# PCM2704_Test_v1.net
KiCad netlist of a schematic drawn in EAGLE
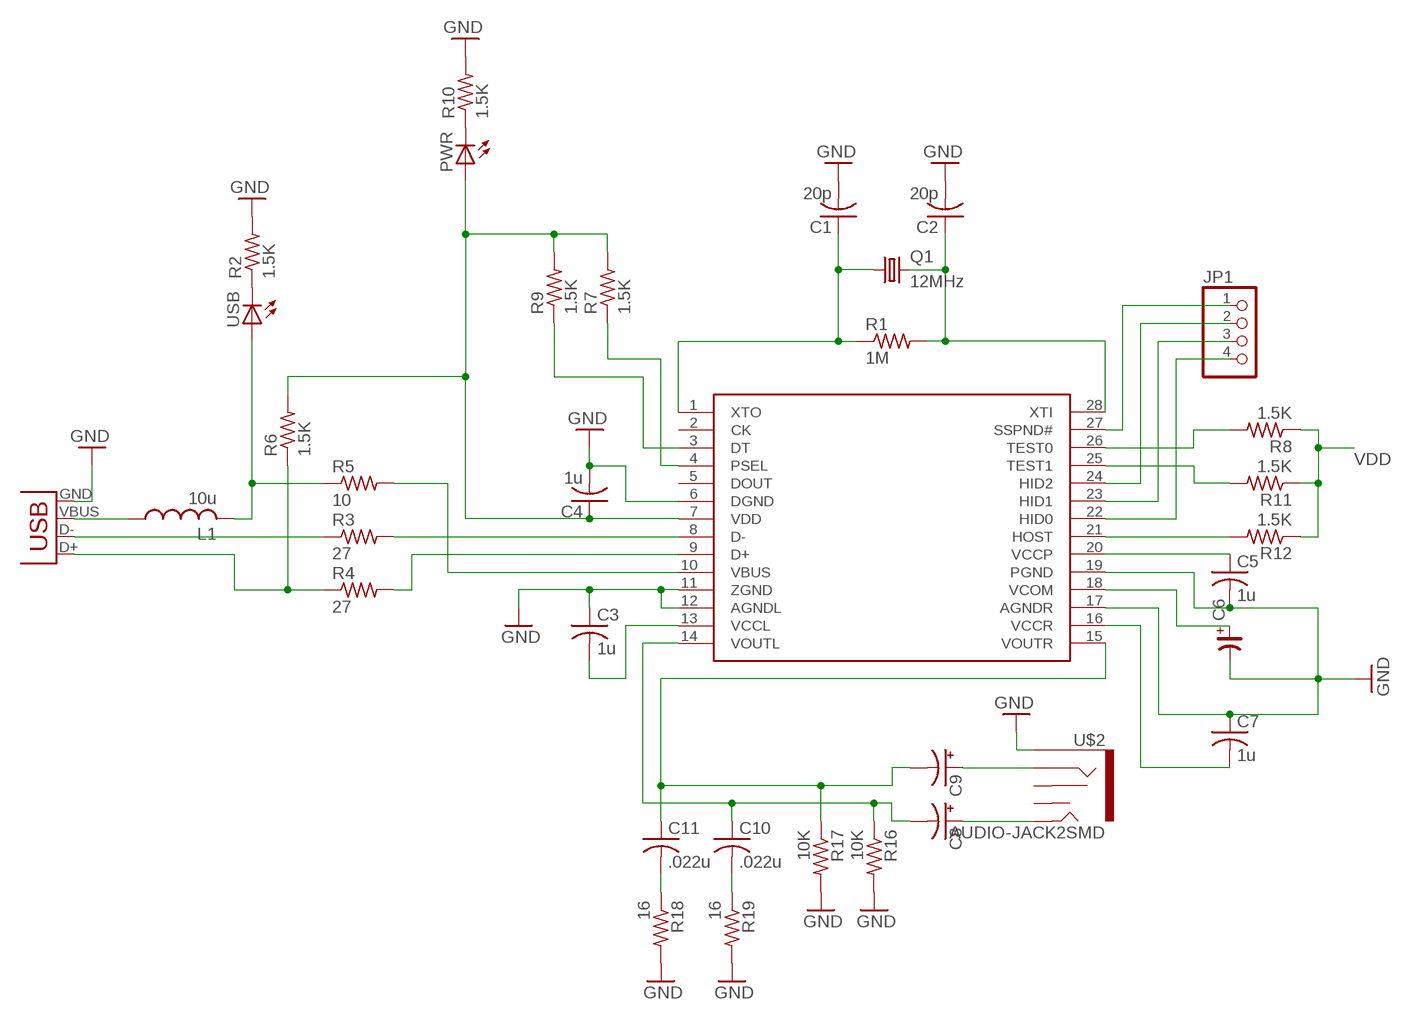
[diagram p0: schematic, sheet 1]

(export (version "E")
  (design (tool "Eeschema 10.0.6"))
  (components
    (comp (ref "C1")
      (value "20p")
      (footprint "eagle-import:C0603")
      (libsource (lib "eagle-import") (part "C-USC0603"))
    )
    (comp (ref "C2")
      (value "20p")
      (footprint "eagle-import:C0603")
      (libsource (lib "eagle-import") (part "C-USC0603"))
    )
    (comp (ref "C3")
      (value "1u")
      (footprint "eagle-import:C0603")
      (libsource (lib "eagle-import") (part "C-USC0603"))
    )
    (comp (ref "C4")
      (value "1u")
      (footprint "eagle-import:C0603")
      (libsource (lib "eagle-import") (part "C-USC0603"))
    )
    (comp (ref "C5")
      (value "1u")
      (footprint "eagle-import:C0603")
      (libsource (lib "eagle-import") (part "C-USC0603"))
    )
    (comp (ref "C6")
      (value "CP_E-010X030")
      (footprint "eagle-import:CE-010X030")
      (libsource (lib "eagle-import") (part "CP_E-010X030"))
    )
    (comp (ref "C7")
      (value "1u")
      (footprint "eagle-import:C0603")
      (libsource (lib "eagle-import") (part "C-USC0603"))
    )
    (comp (ref "C8")
      (value "CPOL-USE1.8-4")
      (footprint "eagle-import:E1,8-4")
      (libsource (lib "eagle-import") (part "CPOL-USE1.8-4"))
    )
    (comp (ref "C9")
      (value "CPOL-USE1.8-4")
      (footprint "eagle-import:E1,8-4")
      (libsource (lib "eagle-import") (part "CPOL-USE1.8-4"))
    )
    (comp (ref "C10")
      (value ".022u")
      (footprint "eagle-import:C0603")
      (libsource (lib "eagle-import") (part "C-USC0603"))
    )
    (comp (ref "C11")
      (value ".022u")
      (footprint "eagle-import:C0603")
      (libsource (lib "eagle-import") (part "C-USC0603"))
    )
    (comp (ref "JP1")
      (value "PINHD-1X4")
      (footprint "eagle-import:1X04")
      (libsource (lib "eagle-import") (part "PINHD-1X4"))
    )
    (comp (ref "L1")
      (value "10u")
      (footprint "eagle-import:L3225M")
      (libsource (lib "eagle-import") (part "L-USL3225M"))
    )
    (comp (ref "PWR")
      (value "LEDCHIP-LED0603")
      (footprint "eagle-import:CHIP-LED0603")
      (libsource (lib "eagle-import") (part "LEDCHIP-LED0603"))
    )
    (comp (ref "Q1")
      (value "12MHz")
      (footprint "eagle-import:HC49US")
      (libsource (lib "eagle-import") (part "CRYSTALHC49US"))
    )
    (comp (ref "R1")
      (value "1M")
      (footprint "eagle-import:R0603")
      (libsource (lib "eagle-import") (part "R-US_R0603"))
    )
    (comp (ref "R2")
      (value "1.5K")
      (footprint "eagle-import:R0603")
      (libsource (lib "eagle-import") (part "R-US_R0603"))
    )
    (comp (ref "R3")
      (value "27")
      (footprint "eagle-import:R0603")
      (libsource (lib "eagle-import") (part "R-US_R0603"))
    )
    (comp (ref "R4")
      (value "27")
      (footprint "eagle-import:R0603")
      (libsource (lib "eagle-import") (part "R-US_R0603"))
    )
    (comp (ref "R5")
      (value "10")
      (footprint "eagle-import:R0603")
      (libsource (lib "eagle-import") (part "R-US_R0603"))
    )
    (comp (ref "R6")
      (value "1.5K")
      (footprint "eagle-import:R0603")
      (libsource (lib "eagle-import") (part "R-US_R0603"))
    )
    (comp (ref "R7")
      (value "1.5K")
      (footprint "eagle-import:R0603")
      (libsource (lib "eagle-import") (part "R-US_R0603"))
    )
    (comp (ref "R8")
      (value "1.5K")
      (footprint "eagle-import:R0603")
      (libsource (lib "eagle-import") (part "R-US_R0603"))
    )
    (comp (ref "R9")
      (value "1.5K")
      (footprint "eagle-import:R0603")
      (libsource (lib "eagle-import") (part "R-US_R0603"))
    )
    (comp (ref "R10")
      (value "1.5K")
      (footprint "eagle-import:R0603")
      (libsource (lib "eagle-import") (part "R-US_R0603"))
    )
    (comp (ref "R11")
      (value "1.5K")
      (footprint "eagle-import:R0603")
      (libsource (lib "eagle-import") (part "R-US_R0603"))
    )
    (comp (ref "R12")
      (value "1.5K")
      (footprint "eagle-import:R0603")
      (libsource (lib "eagle-import") (part "R-US_R0603"))
    )
    (comp (ref "R16")
      (value "10K")
      (footprint "eagle-import:R0603")
      (libsource (lib "eagle-import") (part "R-US_R0603"))
    )
    (comp (ref "R17")
      (value "10K")
      (footprint "eagle-import:R0603")
      (libsource (lib "eagle-import") (part "R-US_R0603"))
    )
    (comp (ref "R18")
      (value "16")
      (footprint "eagle-import:R0603")
      (libsource (lib "eagle-import") (part "R-US_R0603"))
    )
    (comp (ref "R19")
      (value "16")
      (footprint "eagle-import:R0603")
      (libsource (lib "eagle-import") (part "R-US_R0603"))
    )
    (comp (ref "U$1")
      (value "PCM2704C")
      (footprint "eagle-import:PCM2704C")
      (libsource (lib "eagle-import") (part "PCM2704C"))
    )
    (comp (ref "U$2")
      (value "AUDIO-JACK2SMD")
      (footprint "eagle-import:AUDIO-JACK-3.5MM-SMD")
      (libsource (lib "eagle-import") (part "AUDIO-JACK2SMD"))
    )
    (comp (ref "USB")
      (value "LEDCHIP-LED0603")
      (footprint "eagle-import:CHIP-LED0603")
      (libsource (lib "eagle-import") (part "LEDCHIP-LED0603"))
    )
    (comp (ref "X1")
      (value "USB-MB-S")
      (footprint "eagle-import:USB-MB-S")
      (libsource (lib "eagle-import") (part "USB-MB-S"))
    )
  )
  (nets
    (net (code "1") (name "/VDD") (class "Default")
      (node (ref "C4") (pin "1") (pinfunction "1_1") (pintype "passive"))
      (node (ref "PWR") (pin "A") (pinfunction "A_A") (pintype "passive"))
      (node (ref "R11") (pin "1") (pinfunction "1_1") (pintype "passive"))
      (node (ref "R12") (pin "1") (pinfunction "1_1") (pintype "passive"))
      (node (ref "R6") (pin "2") (pinfunction "2_2") (pintype "passive"))
      (node (ref "R7") (pin "2") (pinfunction "2_2") (pintype "passive"))
      (node (ref "R8") (pin "1") (pinfunction "1_1") (pintype "passive"))
      (node (ref "R9") (pin "2") (pinfunction "2_2") (pintype "passive"))
      (node (ref "U$1") (pin "7") (pinfunction "VDD_7") (pintype "bidirectional"))
    )
    (net (code "2") (name "GND") (class "Default")
      (node (ref "C1") (pin "2") (pinfunction "2_2") (pintype "passive"))
      (node (ref "C2") (pin "2") (pinfunction "2_2") (pintype "passive"))
      (node (ref "C3") (pin "1") (pinfunction "1_1") (pintype "passive"))
      (node (ref "C4") (pin "2") (pinfunction "2_2") (pintype "passive"))
      (node (ref "C5") (pin "2") (pinfunction "2_2") (pintype "passive"))
      (node (ref "C6") (pin "-") (pinfunction "-_-") (pintype "passive"))
      (node (ref "C7") (pin "1") (pinfunction "1_1") (pintype "passive"))
      (node (ref "R10") (pin "2") (pinfunction "2_2") (pintype "passive"))
      (node (ref "R16") (pin "2") (pinfunction "2_2") (pintype "passive"))
      (node (ref "R17") (pin "2") (pinfunction "2_2") (pintype "passive"))
      (node (ref "R18") (pin "2") (pinfunction "2_2") (pintype "passive"))
      (node (ref "R19") (pin "2") (pinfunction "2_2") (pintype "passive"))
      (node (ref "R2") (pin "2") (pinfunction "2_2") (pintype "passive"))
      (node (ref "U$1") (pin "11") (pinfunction "ZGND_11") (pintype "bidirectional"))
      (node (ref "U$1") (pin "12") (pinfunction "AGNDL_12") (pintype "bidirectional"))
      (node (ref "U$1") (pin "17") (pinfunction "AGNDR_17") (pintype "bidirectional"))
      (node (ref "U$1") (pin "19") (pinfunction "PGND_19") (pintype "bidirectional"))
      (node (ref "U$1") (pin "6") (pinfunction "DGND_6") (pintype "bidirectional"))
      (node (ref "U$2") (pin "SLEEVE") (pinfunction "SLEEVE_SLEEVE") (pintype "bidirectional"))
      (node (ref "X1") (pin "GND") (pinfunction "GND_GND") (pintype "bidirectional"))
    )
    (net (code "3") (name "Net-(C8-Pad+)") (class "Default")
      (node (ref "C8") (pin "+") (pinfunction "+_+") (pintype "passive"))
      (node (ref "U$2") (pin "TIP") (pinfunction "TIP_TIP") (pintype "bidirectional"))
    )
    (net (code "4") (name "Net-(C9-Pad+)") (class "Default")
      (node (ref "C9") (pin "+") (pinfunction "+_+") (pintype "passive"))
      (node (ref "U$2") (pin "RING") (pinfunction "RING_RING") (pintype "bidirectional"))
    )
    (net (code "5") (name "Net-(C10-Pad2)") (class "Default")
      (node (ref "C10") (pin "2") (pinfunction "2_2") (pintype "passive"))
      (node (ref "R19") (pin "1") (pinfunction "1_1") (pintype "passive"))
    )
    (net (code "6") (name "Net-(C11-Pad2)") (class "Default")
      (node (ref "C11") (pin "2") (pinfunction "2_2") (pintype "passive"))
      (node (ref "R18") (pin "1") (pinfunction "1_1") (pintype "passive"))
    )
    (net (code "7") (name "Net-(L1-Pad1)") (class "Default")
      (node (ref "L1") (pin "1") (pinfunction "1_1") (pintype "passive"))
      (node (ref "X1") (pin "VBUS") (pinfunction "VBUS_VBUS") (pintype "bidirectional"))
    )
    (net (code "8") (name "Net-(L1-Pad2)") (class "Default")
      (node (ref "L1") (pin "2") (pinfunction "2_2") (pintype "passive"))
      (node (ref "R5") (pin "1") (pinfunction "1_1") (pintype "passive"))
      (node (ref "USB") (pin "A") (pinfunction "A_A") (pintype "passive"))
    )
    (net (code "9") (name "Net-(PWR-PadC)") (class "Default")
      (node (ref "PWR") (pin "C") (pinfunction "C_C") (pintype "passive"))
      (node (ref "R10") (pin "1") (pinfunction "1_1") (pintype "passive"))
    )
    (net (code "10") (name "Net-(R2-Pad1)") (class "Default")
      (node (ref "R2") (pin "1") (pinfunction "1_1") (pintype "passive"))
      (node (ref "USB") (pin "C") (pinfunction "C_C") (pintype "passive"))
    )
    (net (code "11") (name "Net-(R3-Pad1)") (class "Default")
      (node (ref "R3") (pin "1") (pinfunction "1_1") (pintype "passive"))
      (node (ref "X1") (pin "D-") (pinfunction "D-_D-") (pintype "bidirectional"))
    )
    (net (code "12") (name "Net-(R4-Pad1)") (class "Default")
      (node (ref "R4") (pin "1") (pinfunction "1_1") (pintype "passive"))
      (node (ref "R6") (pin "1") (pinfunction "1_1") (pintype "passive"))
      (node (ref "X1") (pin "D+") (pinfunction "D+_D+") (pintype "bidirectional"))
    )
    (net (code "13") (name "Net-(U$1-D+)") (class "Default")
      (node (ref "R4") (pin "2") (pinfunction "2_2") (pintype "passive"))
      (node (ref "U$1") (pin "9") (pinfunction "D+_9") (pintype "bidirectional"))
    )
    (net (code "14") (name "Net-(U$1-D-)") (class "Default")
      (node (ref "R3") (pin "2") (pinfunction "2_2") (pintype "passive"))
      (node (ref "U$1") (pin "8") (pinfunction "D-_8") (pintype "bidirectional"))
    )
    (net (code "15") (name "Net-(U$1-DT)") (class "Default")
      (node (ref "R9") (pin "1") (pinfunction "1_1") (pintype "passive"))
      (node (ref "U$1") (pin "3") (pinfunction "DT_3") (pintype "bidirectional"))
    )
    (net (code "16") (name "Net-(U$1-HID0)") (class "Default")
      (node (ref "JP1") (pin "4") (pinfunction "4_4") (pintype "passive"))
      (node (ref "U$1") (pin "22") (pinfunction "HID0_22") (pintype "bidirectional"))
    )
    (net (code "17") (name "Net-(U$1-HID1)") (class "Default")
      (node (ref "JP1") (pin "3") (pinfunction "3_3") (pintype "passive"))
      (node (ref "U$1") (pin "23") (pinfunction "HID1_23") (pintype "bidirectional"))
    )
    (net (code "18") (name "Net-(U$1-HID2)") (class "Default")
      (node (ref "JP1") (pin "2") (pinfunction "2_2") (pintype "passive"))
      (node (ref "U$1") (pin "24") (pinfunction "HID2_24") (pintype "bidirectional"))
    )
    (net (code "19") (name "Net-(U$1-HOST)") (class "Default")
      (node (ref "R12") (pin "2") (pinfunction "2_2") (pintype "passive"))
      (node (ref "U$1") (pin "21") (pinfunction "HOST_21") (pintype "bidirectional"))
    )
    (net (code "20") (name "Net-(U$1-PSEL)") (class "Default")
      (node (ref "R7") (pin "1") (pinfunction "1_1") (pintype "passive"))
      (node (ref "U$1") (pin "4") (pinfunction "PSEL_4") (pintype "bidirectional"))
    )
    (net (code "21") (name "Net-(U$1-SSPND#)") (class "Default")
      (node (ref "JP1") (pin "1") (pinfunction "1_1") (pintype "passive"))
      (node (ref "U$1") (pin "27") (pinfunction "SSPND#_27") (pintype "bidirectional"))
    )
    (net (code "22") (name "Net-(U$1-TEST0)") (class "Default")
      (node (ref "R8") (pin "2") (pinfunction "2_2") (pintype "passive"))
      (node (ref "U$1") (pin "26") (pinfunction "TEST0_26") (pintype "bidirectional"))
    )
    (net (code "23") (name "Net-(U$1-TEST1)") (class "Default")
      (node (ref "R11") (pin "2") (pinfunction "2_2") (pintype "passive"))
      (node (ref "U$1") (pin "25") (pinfunction "TEST1_25") (pintype "bidirectional"))
    )
    (net (code "24") (name "Net-(U$1-VBUS)") (class "Default")
      (node (ref "R5") (pin "2") (pinfunction "2_2") (pintype "passive"))
      (node (ref "U$1") (pin "10") (pinfunction "VBUS_10") (pintype "bidirectional"))
    )
    (net (code "25") (name "Net-(U$1-VCCL)") (class "Default")
      (node (ref "C3") (pin "2") (pinfunction "2_2") (pintype "passive"))
      (node (ref "U$1") (pin "13") (pinfunction "VCCL_13") (pintype "bidirectional"))
    )
    (net (code "26") (name "Net-(U$1-VCCP)") (class "Default")
      (node (ref "C5") (pin "1") (pinfunction "1_1") (pintype "passive"))
      (node (ref "U$1") (pin "20") (pinfunction "VCCP_20") (pintype "bidirectional"))
    )
    (net (code "27") (name "Net-(U$1-VCCR)") (class "Default")
      (node (ref "C7") (pin "2") (pinfunction "2_2") (pintype "passive"))
      (node (ref "U$1") (pin "16") (pinfunction "VCCR_16") (pintype "bidirectional"))
    )
    (net (code "28") (name "Net-(U$1-VCOM)") (class "Default")
      (node (ref "C6") (pin "+") (pinfunction "+_+") (pintype "passive"))
      (node (ref "U$1") (pin "18") (pinfunction "VCOM_18") (pintype "bidirectional"))
    )
    (net (code "29") (name "Net-(U$1-VOUTL)") (class "Default")
      (node (ref "C10") (pin "1") (pinfunction "1_1") (pintype "passive"))
      (node (ref "C8") (pin "-") (pinfunction "-_-") (pintype "passive"))
      (node (ref "R16") (pin "1") (pinfunction "1_1") (pintype "passive"))
      (node (ref "U$1") (pin "14") (pinfunction "VOUTL_14") (pintype "bidirectional"))
    )
    (net (code "30") (name "Net-(U$1-VOUTR)") (class "Default")
      (node (ref "C11") (pin "1") (pinfunction "1_1") (pintype "passive"))
      (node (ref "C9") (pin "-") (pinfunction "-_-") (pintype "passive"))
      (node (ref "R17") (pin "1") (pinfunction "1_1") (pintype "passive"))
      (node (ref "U$1") (pin "15") (pinfunction "VOUTR_15") (pintype "bidirectional"))
    )
    (net (code "31") (name "Net-(U$1-XTI)") (class "Default")
      (node (ref "C2") (pin "1") (pinfunction "1_1") (pintype "passive"))
      (node (ref "Q1") (pin "2") (pinfunction "2_2") (pintype "passive"))
      (node (ref "R1") (pin "2") (pinfunction "2_2") (pintype "passive"))
      (node (ref "U$1") (pin "28") (pinfunction "XTI_28") (pintype "bidirectional"))
    )
    (net (code "32") (name "Net-(U$1-XTO)") (class "Default")
      (node (ref "C1") (pin "1") (pinfunction "1_1") (pintype "passive"))
      (node (ref "Q1") (pin "1") (pinfunction "1_1") (pintype "passive"))
      (node (ref "R1") (pin "1") (pinfunction "1_1") (pintype "passive"))
      (node (ref "U$1") (pin "1") (pinfunction "XTO_1") (pintype "bidirectional"))
    )
    (net (code "33") (name "unconnected-(U$1-CK-Pad2)") (class "Default")
      (node (ref "U$1") (pin "2") (pinfunction "CK_2") (pintype "bidirectional"))
    )
    (net (code "34") (name "unconnected-(U$1-DOUT-Pad5)") (class "Default")
      (node (ref "U$1") (pin "5") (pinfunction "DOUT_5") (pintype "bidirectional"))
    )
    (net (code "35") (name "unconnected-(U$2-PadRSH)") (class "Default")
      (node (ref "U$2") (pin "RSH") (pinfunction "RSH_RSH") (pintype "bidirectional"))
    )
    (net (code "36") (name "unconnected-(U$2-PadTSH)") (class "Default")
      (node (ref "U$2") (pin "TSH") (pinfunction "TSH_TSH") (pintype "bidirectional"))
    )
  )
)
